# final.net
KiCad netlist of a schematic drawn in EAGLE
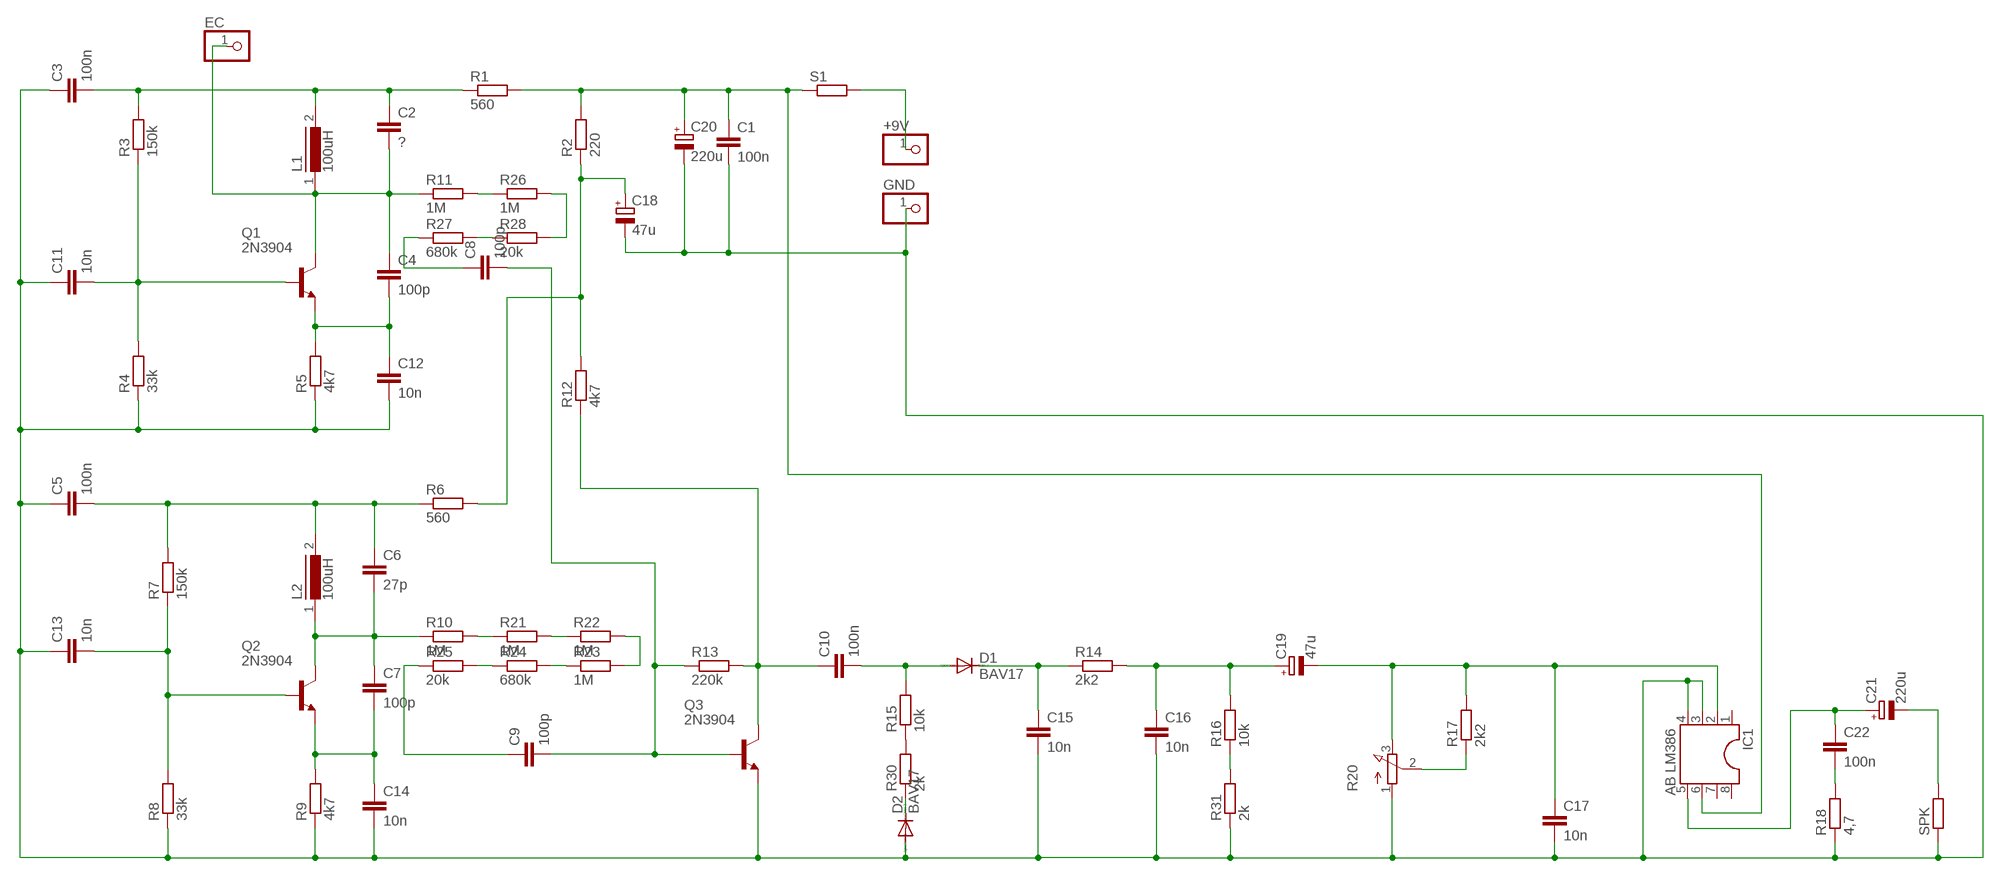
[diagram p0: schematic, sheet 1]

(export (version "E")
  (design (tool "Eeschema 10.0.6"))
  (components
    (comp (ref "+9V")
      (value "PINHD-1X1")
      (footprint "eagle-import:1X01")
      (libsource (lib "eagle-import") (part "PINHD-1X1"))
    )
    (comp (ref "C1")
      (value "100n")
      (footprint "eagle-import:C025-025X050")
      (libsource (lib "eagle-import") (part "C-EU025-025X050"))
    )
    (comp (ref "C2")
      (value "?")
      (footprint "eagle-import:C025-025X050")
      (libsource (lib "eagle-import") (part "C-EU025-025X050"))
    )
    (comp (ref "C3")
      (value "100n")
      (footprint "eagle-import:C025-025X050")
      (libsource (lib "eagle-import") (part "C-EU025-025X050"))
    )
    (comp (ref "C4")
      (value "100p")
      (footprint "eagle-import:C025-025X050")
      (libsource (lib "eagle-import") (part "C-EU025-025X050"))
    )
    (comp (ref "C5")
      (value "100n")
      (footprint "eagle-import:C025-025X050")
      (libsource (lib "eagle-import") (part "C-EU025-025X050"))
    )
    (comp (ref "C6")
      (value "27p")
      (footprint "eagle-import:C025-025X050")
      (libsource (lib "eagle-import") (part "C-EU025-025X050"))
    )
    (comp (ref "C7")
      (value "100p")
      (footprint "eagle-import:C025-025X050")
      (libsource (lib "eagle-import") (part "C-EU025-025X050"))
    )
    (comp (ref "C8")
      (value "100p")
      (footprint "eagle-import:C025-025X050")
      (libsource (lib "eagle-import") (part "C-EU025-025X050"))
    )
    (comp (ref "C9")
      (value "100p")
      (footprint "eagle-import:C025-025X050")
      (libsource (lib "eagle-import") (part "C-EU025-025X050"))
    )
    (comp (ref "C10")
      (value "100n")
      (footprint "eagle-import:C025-025X050")
      (libsource (lib "eagle-import") (part "C-EU025-025X050"))
    )
    (comp (ref "C11")
      (value "10n")
      (footprint "eagle-import:C050-025X075")
      (libsource (lib "eagle-import") (part "C-EU050-025X075"))
    )
    (comp (ref "C12")
      (value "10n")
      (footprint "eagle-import:C050-025X075")
      (libsource (lib "eagle-import") (part "C-EU050-025X075"))
    )
    (comp (ref "C13")
      (value "10n")
      (footprint "eagle-import:C050-025X075")
      (libsource (lib "eagle-import") (part "C-EU050-025X075"))
    )
    (comp (ref "C14")
      (value "10n")
      (footprint "eagle-import:C050-025X075")
      (libsource (lib "eagle-import") (part "C-EU050-025X075"))
    )
    (comp (ref "C15")
      (value "10n")
      (footprint "eagle-import:C050-025X075")
      (libsource (lib "eagle-import") (part "C-EU050-025X075"))
    )
    (comp (ref "C16")
      (value "10n")
      (footprint "eagle-import:C050-025X075")
      (libsource (lib "eagle-import") (part "C-EU050-025X075"))
    )
    (comp (ref "C17")
      (value "10n")
      (footprint "eagle-import:C050-025X075")
      (libsource (lib "eagle-import") (part "C-EU050-025X075"))
    )
    (comp (ref "C18")
      (value "47u")
      (footprint "eagle-import:E5-6")
      (libsource (lib "eagle-import") (part "CPOL-EUE5-6"))
    )
    (comp (ref "C19")
      (value "47u")
      (footprint "eagle-import:E5-6")
      (libsource (lib "eagle-import") (part "CPOL-EUE5-6"))
    )
    (comp (ref "C20")
      (value "220u")
      (footprint "eagle-import:E5-8,5")
      (libsource (lib "eagle-import") (part "CPOL-EUE5-8.5"))
    )
    (comp (ref "C21")
      (value "220u")
      (footprint "eagle-import:E5-8,5")
      (libsource (lib "eagle-import") (part "CPOL-EUE5-8.5"))
    )
    (comp (ref "C22")
      (value "100n")
      (footprint "eagle-import:C025-025X050")
      (libsource (lib "eagle-import") (part "C-EU025-025X050"))
    )
    (comp (ref "D1")
      (value "BAV17")
      (footprint "eagle-import:DO35-10")
      (libsource (lib "eagle-import") (part "BAV17"))
    )
    (comp (ref "D2")
      (value "BAV17")
      (footprint "eagle-import:DO35-10")
      (libsource (lib "eagle-import") (part "BAV17"))
    )
    (comp (ref "EC")
      (value "PINHD-1X1")
      (footprint "eagle-import:1X01")
      (libsource (lib "eagle-import") (part "PINHD-1X1"))
    )
    (comp (ref "GND")
      (value "PINHD-1X1")
      (footprint "eagle-import:1X01")
      (libsource (lib "eagle-import") (part "PINHD-1X1"))
    )
    (comp (ref "IC1")
      (value "AB LM386")
      (footprint "eagle-import:DIL08")
      (libsource (lib "eagle-import") (part "DIL8"))
    )
    (comp (ref "L1")
      (value "100uH")
      (footprint "eagle-import:82114R")
      (libsource (lib "eagle-import") (part "82114R"))
    )
    (comp (ref "L2")
      (value "100uH")
      (footprint "eagle-import:82114R")
      (libsource (lib "eagle-import") (part "82114R"))
    )
    (comp (ref "Q1")
      (value "2N3904")
      (footprint "eagle-import:TO92")
      (libsource (lib "eagle-import") (part "2N3904"))
    )
    (comp (ref "Q2")
      (value "2N3904")
      (footprint "eagle-import:TO92")
      (libsource (lib "eagle-import") (part "2N3904"))
    )
    (comp (ref "Q3")
      (value "2N3904")
      (footprint "eagle-import:TO92")
      (libsource (lib "eagle-import") (part "2N3904"))
    )
    (comp (ref "R1")
      (value "560")
      (footprint "eagle-import:0204_5")
      (libsource (lib "eagle-import") (part "R-EU_0204/5"))
    )
    (comp (ref "R2")
      (value "220")
      (footprint "eagle-import:0204_5")
      (libsource (lib "eagle-import") (part "R-EU_0204/5"))
    )
    (comp (ref "R3")
      (value "150k")
      (footprint "eagle-import:0204_5")
      (libsource (lib "eagle-import") (part "R-EU_0204/5"))
    )
    (comp (ref "R4")
      (value "33k")
      (footprint "eagle-import:0204_5")
      (libsource (lib "eagle-import") (part "R-EU_0204/5"))
    )
    (comp (ref "R5")
      (value "4k7")
      (footprint "eagle-import:0204_5")
      (libsource (lib "eagle-import") (part "R-EU_0204/5"))
    )
    (comp (ref "R6")
      (value "560")
      (footprint "eagle-import:0204_5")
      (libsource (lib "eagle-import") (part "R-EU_0204/5"))
    )
    (comp (ref "R7")
      (value "150k")
      (footprint "eagle-import:0204_5")
      (libsource (lib "eagle-import") (part "R-EU_0204/5"))
    )
    (comp (ref "R8")
      (value "33k")
      (footprint "eagle-import:0204_5")
      (libsource (lib "eagle-import") (part "R-EU_0204/5"))
    )
    (comp (ref "R9")
      (value "4k7")
      (footprint "eagle-import:0204_5")
      (libsource (lib "eagle-import") (part "R-EU_0204/5"))
    )
    (comp (ref "R10")
      (value "1M")
      (footprint "eagle-import:0204_5")
      (libsource (lib "eagle-import") (part "R-EU_0204/5"))
    )
    (comp (ref "R11")
      (value "1M")
      (footprint "eagle-import:0204_5")
      (libsource (lib "eagle-import") (part "R-EU_0204/5"))
    )
    (comp (ref "R12")
      (value "4k7")
      (footprint "eagle-import:0204_5")
      (libsource (lib "eagle-import") (part "R-EU_0204/5"))
    )
    (comp (ref "R13")
      (value "220k")
      (footprint "eagle-import:0204_5")
      (libsource (lib "eagle-import") (part "R-EU_0204/5"))
    )
    (comp (ref "R14")
      (value "2k2")
      (footprint "eagle-import:0204_5")
      (libsource (lib "eagle-import") (part "R-EU_0204/5"))
    )
    (comp (ref "R15")
      (value "10k")
      (footprint "eagle-import:0204_5")
      (libsource (lib "eagle-import") (part "R-EU_0204/5"))
    )
    (comp (ref "R16")
      (value "10k")
      (footprint "eagle-import:0204_5")
      (libsource (lib "eagle-import") (part "R-EU_0204/5"))
    )
    (comp (ref "R17")
      (value "2k2")
      (footprint "eagle-import:0204_5")
      (libsource (lib "eagle-import") (part "R-EU_0204/5"))
    )
    (comp (ref "R18")
      (value "4,7")
      (footprint "eagle-import:0204_5")
      (libsource (lib "eagle-import") (part "R-EU_0204/5"))
    )
    (comp (ref "R20")
      (value "3RP/1610N")
      (footprint "eagle-import:3RP_1610N")
      (libsource (lib "eagle-import") (part "3RP/1610N"))
    )
    (comp (ref "R21")
      (value "1M")
      (footprint "eagle-import:0204_5")
      (libsource (lib "eagle-import") (part "R-EU_0204/5"))
    )
    (comp (ref "R22")
      (value "1M")
      (footprint "eagle-import:0204_5")
      (libsource (lib "eagle-import") (part "R-EU_0204/5"))
    )
    (comp (ref "R23")
      (value "1M")
      (footprint "eagle-import:0204_5")
      (libsource (lib "eagle-import") (part "R-EU_0204/5"))
    )
    (comp (ref "R24")
      (value "680k")
      (footprint "eagle-import:0204_5")
      (libsource (lib "eagle-import") (part "R-EU_0204/5"))
    )
    (comp (ref "R25")
      (value "20k")
      (footprint "eagle-import:0204_5")
      (libsource (lib "eagle-import") (part "R-EU_0204/5"))
    )
    (comp (ref "R26")
      (value "1M")
      (footprint "eagle-import:0204_5")
      (libsource (lib "eagle-import") (part "R-EU_0204/5"))
    )
    (comp (ref "R27")
      (value "680k")
      (footprint "eagle-import:0204_5")
      (libsource (lib "eagle-import") (part "R-EU_0204/5"))
    )
    (comp (ref "R28")
      (value "20k")
      (footprint "eagle-import:0204_5")
      (libsource (lib "eagle-import") (part "R-EU_0204/5"))
    )
    (comp (ref "R30")
      (value "2k")
      (footprint "eagle-import:0204_5")
      (libsource (lib "eagle-import") (part "R-EU_0204/5"))
    )
    (comp (ref "R31")
      (value "2k")
      (footprint "eagle-import:0204_5")
      (libsource (lib "eagle-import") (part "R-EU_0204/5"))
    )
    (comp (ref "S1")
      (value "R-EU_0204/5")
      (footprint "eagle-import:0204_5")
      (libsource (lib "eagle-import") (part "R-EU_0204/5"))
    )
    (comp (ref "SPK")
      (value "R-EU_0204/5")
      (footprint "eagle-import:0204_5")
      (libsource (lib "eagle-import") (part "R-EU_0204/5"))
    )
  )
  (nets
    (net (code "1") (name "Net-(+9V-Pad1)") (class "Default")
      (node (ref "+9V") (pin "1") (pinfunction "1_1") (pintype "passive"))
      (node (ref "S1") (pin "2") (pinfunction "2_2") (pintype "passive"))
    )
    (net (code "2") (name "Net-(C1-Pad1)") (class "Default")
      (node (ref "C1") (pin "1") (pinfunction "1_1") (pintype "passive"))
      (node (ref "C20") (pin "+") (pinfunction "+_+") (pintype "passive"))
      (node (ref "IC1") (pin "6") (pinfunction "6_6") (pintype "passive"))
      (node (ref "R1") (pin "2") (pinfunction "2_2") (pintype "passive"))
      (node (ref "R2") (pin "2") (pinfunction "2_2") (pintype "passive"))
      (node (ref "S1") (pin "1") (pinfunction "1_1") (pintype "passive"))
    )
    (net (code "3") (name "Net-(C2-Pad1)") (class "Default")
      (node (ref "C2") (pin "1") (pinfunction "1_1") (pintype "passive"))
      (node (ref "C3") (pin "2") (pinfunction "2_2") (pintype "passive"))
      (node (ref "L1") (pin "2") (pinfunction "2_2") (pintype "passive"))
      (node (ref "R1") (pin "1") (pinfunction "1_1") (pintype "passive"))
      (node (ref "R3") (pin "2") (pinfunction "2_2") (pintype "passive"))
    )
    (net (code "4") (name "Net-(C5-Pad2)") (class "Default")
      (node (ref "C5") (pin "2") (pinfunction "2_2") (pintype "passive"))
      (node (ref "C6") (pin "1") (pinfunction "1_1") (pintype "passive"))
      (node (ref "L2") (pin "2") (pinfunction "2_2") (pintype "passive"))
      (node (ref "R6") (pin "1") (pinfunction "1_1") (pintype "passive"))
      (node (ref "R7") (pin "2") (pinfunction "2_2") (pintype "passive"))
    )
    (net (code "5") (name "Net-(C8-Pad1)") (class "Default")
      (node (ref "C8") (pin "1") (pinfunction "1_1") (pintype "passive"))
      (node (ref "R27") (pin "1") (pinfunction "1_1") (pintype "passive"))
    )
    (net (code "6") (name "Net-(C9-Pad1)") (class "Default")
      (node (ref "C9") (pin "1") (pinfunction "1_1") (pintype "passive"))
      (node (ref "R25") (pin "1") (pinfunction "1_1") (pintype "passive"))
    )
    (net (code "7") (name "Net-(C10-Pad2)") (class "Default")
      (node (ref "C10") (pin "2") (pinfunction "2_2") (pintype "passive"))
      (node (ref "D1") (pin "A") (pinfunction "A_A") (pintype "passive"))
      (node (ref "R15") (pin "2") (pinfunction "2_2") (pintype "passive"))
    )
    (net (code "8") (name "Net-(C15-Pad1)") (class "Default")
      (node (ref "C15") (pin "1") (pinfunction "1_1") (pintype "passive"))
      (node (ref "D1") (pin "C") (pinfunction "C_C") (pintype "passive"))
      (node (ref "R14") (pin "1") (pinfunction "1_1") (pintype "passive"))
    )
    (net (code "9") (name "Net-(C16-Pad1)") (class "Default")
      (node (ref "C16") (pin "1") (pinfunction "1_1") (pintype "passive"))
      (node (ref "C19") (pin "+") (pinfunction "+_+") (pintype "passive"))
      (node (ref "R14") (pin "2") (pinfunction "2_2") (pintype "passive"))
      (node (ref "R16") (pin "2") (pinfunction "2_2") (pintype "passive"))
    )
    (net (code "10") (name "Net-(C18-Pad+)") (class "Default")
      (node (ref "C18") (pin "+") (pinfunction "+_+") (pintype "passive"))
      (node (ref "R12") (pin "2") (pinfunction "2_2") (pintype "passive"))
      (node (ref "R2") (pin "1") (pinfunction "1_1") (pintype "passive"))
      (node (ref "R6") (pin "2") (pinfunction "2_2") (pintype "passive"))
    )
    (net (code "11") (name "Net-(C21-Pad+)") (class "Default")
      (node (ref "C21") (pin "+") (pinfunction "+_+") (pintype "passive"))
      (node (ref "C22") (pin "1") (pinfunction "1_1") (pintype "passive"))
      (node (ref "IC1") (pin "5") (pinfunction "5_5") (pintype "passive"))
    )
    (net (code "12") (name "Net-(C21-Pad-)") (class "Default")
      (node (ref "C21") (pin "-") (pinfunction "-_-") (pintype "passive"))
      (node (ref "SPK") (pin "2") (pinfunction "2_2") (pintype "passive"))
    )
    (net (code "13") (name "Net-(C22-Pad2)") (class "Default")
      (node (ref "C22") (pin "2") (pinfunction "2_2") (pintype "passive"))
      (node (ref "R18") (pin "2") (pinfunction "2_2") (pintype "passive"))
    )
    (net (code "14") (name "Net-(D2-PadC)") (class "Default")
      (node (ref "D2") (pin "C") (pinfunction "C_C") (pintype "passive"))
      (node (ref "R30") (pin "1") (pinfunction "1_1") (pintype "passive"))
    )
    (net (code "15") (name "Net-(Q1-B)") (class "Default")
      (node (ref "C11") (pin "2") (pinfunction "2_2") (pintype "passive"))
      (node (ref "Q1") (pin "2") (pinfunction "B_2") (pintype "passive"))
      (node (ref "R3") (pin "1") (pinfunction "1_1") (pintype "passive"))
      (node (ref "R4") (pin "2") (pinfunction "2_2") (pintype "passive"))
    )
    (net (code "16") (name "Net-(Q1-C)") (class "Default")
      (node (ref "C2") (pin "2") (pinfunction "2_2") (pintype "passive"))
      (node (ref "C4") (pin "1") (pinfunction "1_1") (pintype "passive"))
      (node (ref "EC") (pin "1") (pinfunction "1_1") (pintype "passive"))
      (node (ref "L1") (pin "1") (pinfunction "1_1") (pintype "passive"))
      (node (ref "Q1") (pin "1") (pinfunction "C_1") (pintype "passive"))
      (node (ref "R11") (pin "1") (pinfunction "1_1") (pintype "passive"))
    )
    (net (code "17") (name "Net-(Q1-E)") (class "Default")
      (node (ref "C12") (pin "1") (pinfunction "1_1") (pintype "passive"))
      (node (ref "C4") (pin "2") (pinfunction "2_2") (pintype "passive"))
      (node (ref "Q1") (pin "3") (pinfunction "E_3") (pintype "passive"))
      (node (ref "R5") (pin "2") (pinfunction "2_2") (pintype "passive"))
    )
    (net (code "18") (name "Net-(Q2-B)") (class "Default")
      (node (ref "C13") (pin "2") (pinfunction "2_2") (pintype "passive"))
      (node (ref "Q2") (pin "2") (pinfunction "B_2") (pintype "passive"))
      (node (ref "R7") (pin "1") (pinfunction "1_1") (pintype "passive"))
      (node (ref "R8") (pin "2") (pinfunction "2_2") (pintype "passive"))
    )
    (net (code "19") (name "Net-(Q2-C)") (class "Default")
      (node (ref "C6") (pin "2") (pinfunction "2_2") (pintype "passive"))
      (node (ref "C7") (pin "1") (pinfunction "1_1") (pintype "passive"))
      (node (ref "L2") (pin "1") (pinfunction "1_1") (pintype "passive"))
      (node (ref "Q2") (pin "1") (pinfunction "C_1") (pintype "passive"))
      (node (ref "R10") (pin "1") (pinfunction "1_1") (pintype "passive"))
    )
    (net (code "20") (name "Net-(Q2-E)") (class "Default")
      (node (ref "C14") (pin "1") (pinfunction "1_1") (pintype "passive"))
      (node (ref "C7") (pin "2") (pinfunction "2_2") (pintype "passive"))
      (node (ref "Q2") (pin "3") (pinfunction "E_3") (pintype "passive"))
      (node (ref "R9") (pin "2") (pinfunction "2_2") (pintype "passive"))
    )
    (net (code "21") (name "Net-(Q3-B)") (class "Default")
      (node (ref "C8") (pin "2") (pinfunction "2_2") (pintype "passive"))
      (node (ref "C9") (pin "2") (pinfunction "2_2") (pintype "passive"))
      (node (ref "Q3") (pin "2") (pinfunction "B_2") (pintype "passive"))
      (node (ref "R13") (pin "1") (pinfunction "1_1") (pintype "passive"))
    )
    (net (code "22") (name "Net-(Q3-C)") (class "Default")
      (node (ref "C10") (pin "1") (pinfunction "1_1") (pintype "passive"))
      (node (ref "Q3") (pin "1") (pinfunction "C_1") (pintype "passive"))
      (node (ref "R12") (pin "1") (pinfunction "1_1") (pintype "passive"))
      (node (ref "R13") (pin "2") (pinfunction "2_2") (pintype "passive"))
    )
    (net (code "23") (name "Net-(Q3-E)") (class "Default")
      (node (ref "C1") (pin "2") (pinfunction "2_2") (pintype "passive"))
      (node (ref "C11") (pin "1") (pinfunction "1_1") (pintype "passive"))
      (node (ref "C12") (pin "2") (pinfunction "2_2") (pintype "passive"))
      (node (ref "C13") (pin "1") (pinfunction "1_1") (pintype "passive"))
      (node (ref "C14") (pin "2") (pinfunction "2_2") (pintype "passive"))
      (node (ref "C15") (pin "2") (pinfunction "2_2") (pintype "passive"))
      (node (ref "C16") (pin "2") (pinfunction "2_2") (pintype "passive"))
      (node (ref "C17") (pin "2") (pinfunction "2_2") (pintype "passive"))
      (node (ref "C18") (pin "-") (pinfunction "-_-") (pintype "passive"))
      (node (ref "C20") (pin "-") (pinfunction "-_-") (pintype "passive"))
      (node (ref "C3") (pin "1") (pinfunction "1_1") (pintype "passive"))
      (node (ref "C5") (pin "1") (pinfunction "1_1") (pintype "passive"))
      (node (ref "D2") (pin "A") (pinfunction "A_A") (pintype "passive"))
      (node (ref "GND") (pin "1") (pinfunction "1_1") (pintype "passive"))
      (node (ref "IC1") (pin "3") (pinfunction "3_3") (pintype "passive"))
      (node (ref "IC1") (pin "4") (pinfunction "4_4") (pintype "passive"))
      (node (ref "Q3") (pin "3") (pinfunction "E_3") (pintype "passive"))
      (node (ref "R18") (pin "1") (pinfunction "1_1") (pintype "passive"))
      (node (ref "R20") (pin "1") (pinfunction "A_1") (pintype "passive"))
      (node (ref "R31") (pin "1") (pinfunction "1_1") (pintype "passive"))
      (node (ref "R4") (pin "1") (pinfunction "1_1") (pintype "passive"))
      (node (ref "R5") (pin "1") (pinfunction "1_1") (pintype "passive"))
      (node (ref "R8") (pin "1") (pinfunction "1_1") (pintype "passive"))
      (node (ref "R9") (pin "1") (pinfunction "1_1") (pintype "passive"))
      (node (ref "SPK") (pin "1") (pinfunction "1_1") (pintype "passive"))
    )
    (net (code "24") (name "Net-(R10-Pad2)") (class "Default")
      (node (ref "R10") (pin "2") (pinfunction "2_2") (pintype "passive"))
      (node (ref "R21") (pin "1") (pinfunction "1_1") (pintype "passive"))
    )
    (net (code "25") (name "Net-(R11-Pad2)") (class "Default")
      (node (ref "R11") (pin "2") (pinfunction "2_2") (pintype "passive"))
      (node (ref "R26") (pin "1") (pinfunction "1_1") (pintype "passive"))
    )
    (net (code "26") (name "Net-(R15-Pad1)") (class "Default")
      (node (ref "R15") (pin "1") (pinfunction "1_1") (pintype "passive"))
      (node (ref "R30") (pin "2") (pinfunction "2_2") (pintype "passive"))
    )
    (net (code "27") (name "Net-(R16-Pad1)") (class "Default")
      (node (ref "R16") (pin "1") (pinfunction "1_1") (pintype "passive"))
      (node (ref "R31") (pin "2") (pinfunction "2_2") (pintype "passive"))
    )
    (net (code "28") (name "Net-(R20-E)") (class "Default")
      (node (ref "C17") (pin "1") (pinfunction "1_1") (pintype "passive"))
      (node (ref "C19") (pin "-") (pinfunction "-_-") (pintype "passive"))
      (node (ref "IC1") (pin "2") (pinfunction "2_2") (pintype "passive"))
      (node (ref "R17") (pin "2") (pinfunction "2_2") (pintype "passive"))
      (node (ref "R20") (pin "3") (pinfunction "E_3") (pintype "passive"))
    )
    (net (code "29") (name "Net-(R20-S)") (class "Default")
      (node (ref "R17") (pin "1") (pinfunction "1_1") (pintype "passive"))
      (node (ref "R20") (pin "2") (pinfunction "S_2") (pintype "passive"))
    )
    (net (code "30") (name "Net-(R21-Pad2)") (class "Default")
      (node (ref "R21") (pin "2") (pinfunction "2_2") (pintype "passive"))
      (node (ref "R22") (pin "1") (pinfunction "1_1") (pintype "passive"))
    )
    (net (code "31") (name "Net-(R22-Pad2)") (class "Default")
      (node (ref "R22") (pin "2") (pinfunction "2_2") (pintype "passive"))
      (node (ref "R23") (pin "2") (pinfunction "2_2") (pintype "passive"))
    )
    (net (code "32") (name "Net-(R23-Pad1)") (class "Default")
      (node (ref "R23") (pin "1") (pinfunction "1_1") (pintype "passive"))
      (node (ref "R24") (pin "2") (pinfunction "2_2") (pintype "passive"))
    )
    (net (code "33") (name "Net-(R24-Pad1)") (class "Default")
      (node (ref "R24") (pin "1") (pinfunction "1_1") (pintype "passive"))
      (node (ref "R25") (pin "2") (pinfunction "2_2") (pintype "passive"))
    )
    (net (code "34") (name "Net-(R26-Pad2)") (class "Default")
      (node (ref "R26") (pin "2") (pinfunction "2_2") (pintype "passive"))
      (node (ref "R28") (pin "2") (pinfunction "2_2") (pintype "passive"))
    )
    (net (code "35") (name "Net-(R27-Pad2)") (class "Default")
      (node (ref "R27") (pin "2") (pinfunction "2_2") (pintype "passive"))
      (node (ref "R28") (pin "1") (pinfunction "1_1") (pintype "passive"))
    )
    (net (code "36") (name "unconnected-(IC1-Pad1)") (class "Default")
      (node (ref "IC1") (pin "1") (pinfunction "1_1") (pintype "passive"))
    )
    (net (code "37") (name "unconnected-(IC1-Pad7)") (class "Default")
      (node (ref "IC1") (pin "7") (pinfunction "7_7") (pintype "passive"))
    )
    (net (code "38") (name "unconnected-(IC1-Pad8)") (class "Default")
      (node (ref "IC1") (pin "8") (pinfunction "8_8") (pintype "passive"))
    )
  )
)
